# scd4x_rf-bm-2652p2.net
KiCad netlist of a schematic drawn in EAGLE
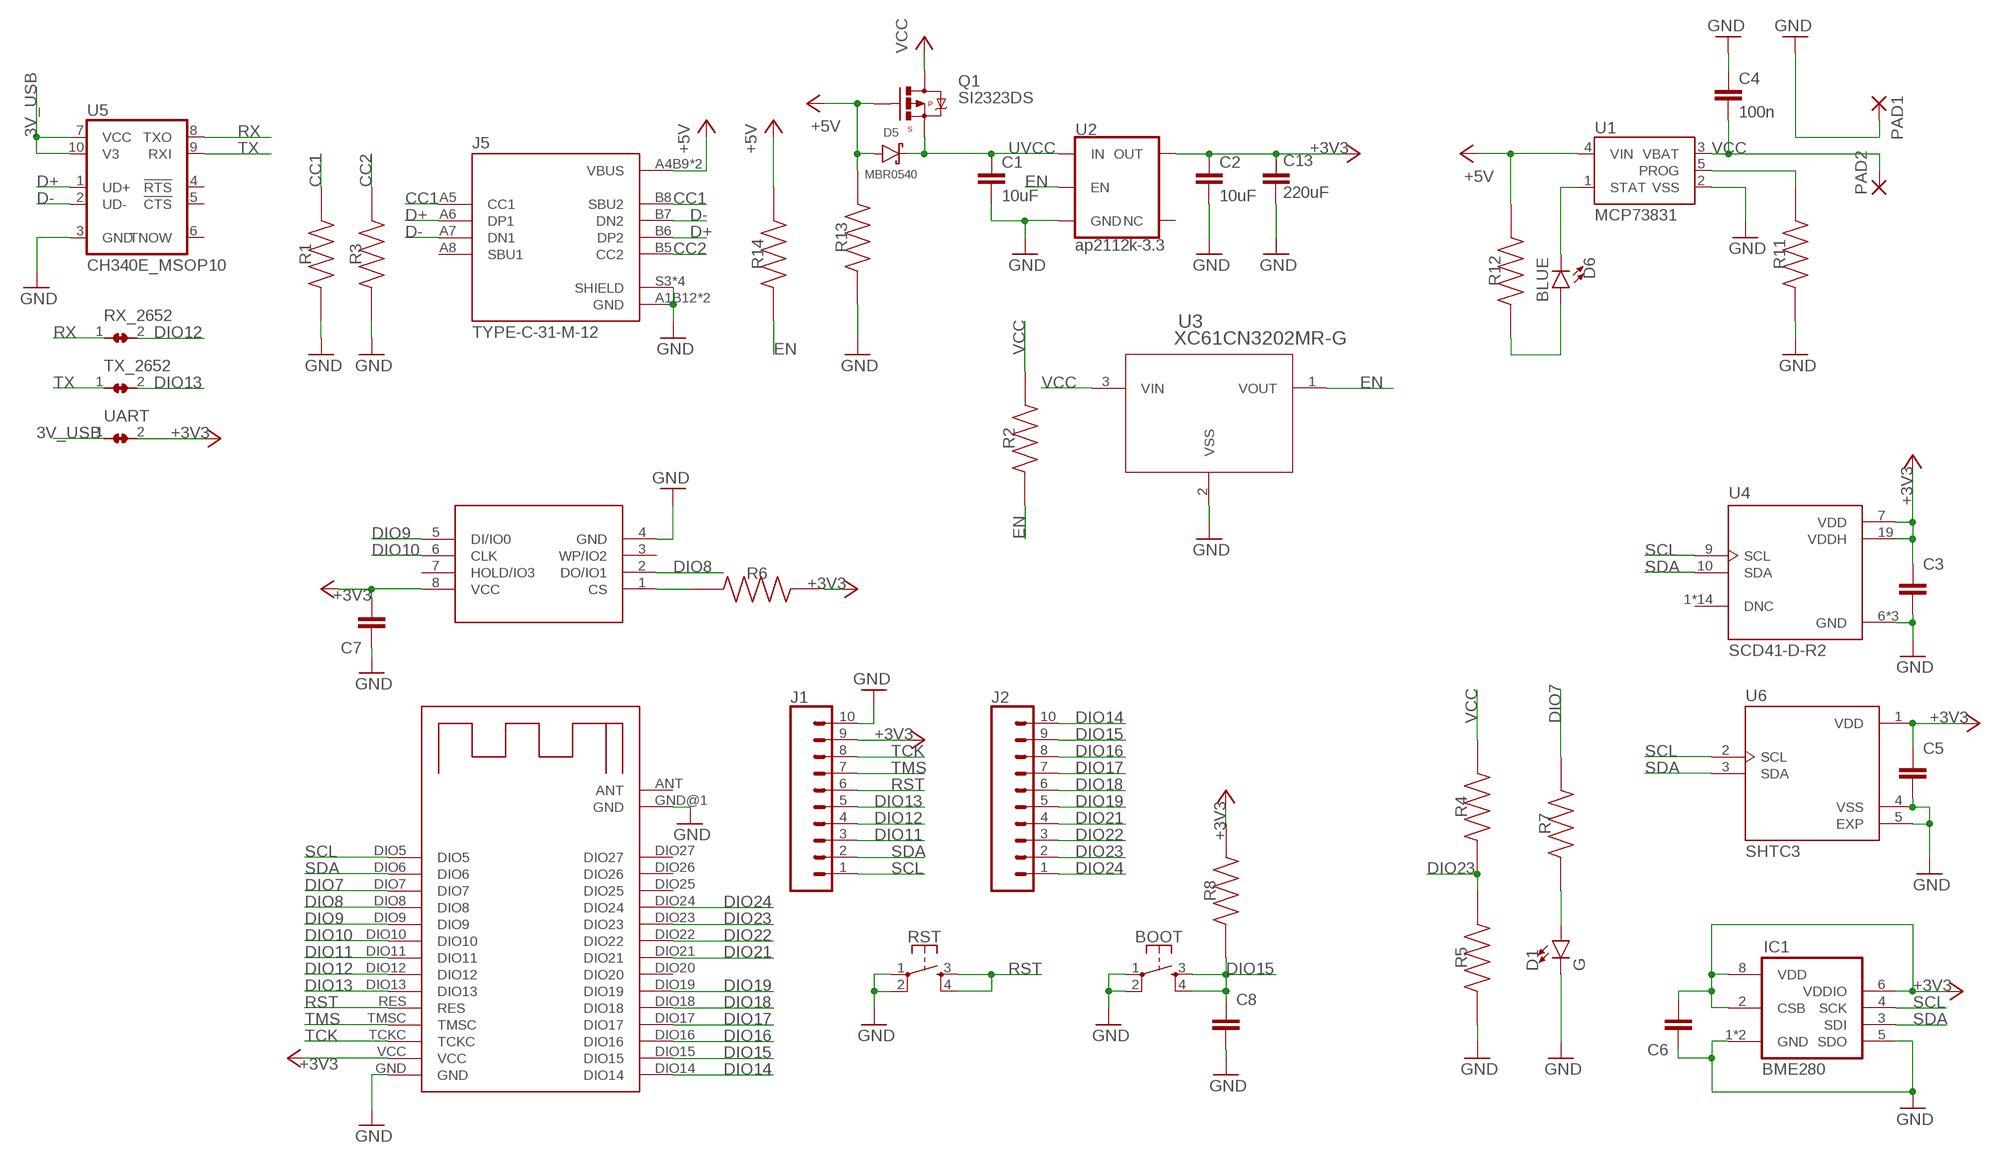
[diagram p0: schematic, sheet 1]

(export (version "E")
  (design (tool "Eeschema 10.0.6"))
  (components
    (comp (ref "BOOT")
      (value "MOMENTARY-SWITCH-SPST-2-SMD-4.6X2.8MM")
      (footprint "eagle-import:TACTILE_SWITCH_SMD_4.6X2.8MM")
      (libsource (lib "eagle-import") (part "MOMENTARY-SWITCH-SPST-2-SMD-4.6X2.8MM"))
    )
    (comp (ref "C1")
      (value "10uF")
      (footprint "eagle-import:0603")
      (libsource (lib "eagle-import") (part "10UF-0603-6.3V-20%"))
    )
    (comp (ref "C2")
      (value "10uF")
      (footprint "eagle-import:0603")
      (libsource (lib "eagle-import") (part "10UF-0603-6.3V-20%"))
    )
    (comp (ref "C3")
      (value "100nF")
      (footprint "eagle-import:CAPC1005X40N")
      (fields (field (name "MF") "Yageo") (field (name "MP") "RC0402FR-073M6L"))
      (libsource (lib "eagle-import") (part "CAP0402"))
    )
    (comp (ref "C4")
      (value "100n")
      (footprint "eagle-import:0603")
      (libsource (lib "eagle-import") (part "10UF-0603-6.3V-20%"))
    )
    (comp (ref "C5")
      (value "100nF")
      (footprint "eagle-import:CAPC1005X40N")
      (fields (field (name "MF") "Yageo") (field (name "MP") "RC0402FR-073M6L"))
      (libsource (lib "eagle-import") (part "CAP0402"))
    )
    (comp (ref "C6")
      (value "100nF")
      (footprint "eagle-import:CAPC1005X40N")
      (fields (field (name "MF") "Yageo") (field (name "MP") "RC0402FR-073M6L"))
      (libsource (lib "eagle-import") (part "CAP0402"))
    )
    (comp (ref "C7")
      (value "100n")
      (footprint "eagle-import:CAPC1005X40N")
      (fields (field (name "MF") "Yageo") (field (name "MP") "RC0402FR-073M6L"))
      (libsource (lib "eagle-import") (part "CAP0402"))
    )
    (comp (ref "C8")
      (value "100nF")
      (footprint "eagle-import:CAPC1005X40N")
      (fields (field (name "MF") "Yageo") (field (name "MP") "RC0402FR-073M6L"))
      (libsource (lib "eagle-import") (part "CAP0402"))
    )
    (comp (ref "C13")
      (value "220uF")
      (footprint "eagle-import:CAPM7343X310")
      (libsource (lib "eagle-import") (part "CTANTALUM-2917(7343-METRIC)_"))
    )
    (comp (ref "D1")
      (value "G")
      (footprint "eagle-import:LED-0603")
      (libsource (lib "eagle-import") (part "LED-BLUE0603"))
    )
    (comp (ref "D5")
      (value "MBR0540")
      (footprint "eagle-import:SOD-323")
      (libsource (lib "eagle-import") (part "DIODE-SCHOTTKY"))
    )
    (comp (ref "D6")
      (value "BLUE")
      (footprint "eagle-import:LED-0603")
      (libsource (lib "eagle-import") (part "LED-BLUE0603"))
    )
    (comp (ref "IC1")
      (value "BME280")
      (footprint "eagle-import:BME280")
      (libsource (lib "eagle-import") (part "BME280"))
    )
    (comp (ref "J1")
      (value "CONN_10NO_SILK_PTH_FEMALE")
      (footprint "eagle-import:1X10_NO_SILK")
      (libsource (lib "eagle-import") (part "CONN_10NO_SILK_PTH_FEMALE"))
    )
    (comp (ref "J2")
      (value "CONN_10NO_SILK_PTH_FEMALE")
      (footprint "eagle-import:1X10_NO_SILK")
      (libsource (lib "eagle-import") (part "CONN_10NO_SILK_PTH_FEMALE"))
    )
    (comp (ref "J5")
      (value "TYPE-C-31-M-12")
      (footprint "eagle-import:HRO_TYPE-C-31-M-12")
      (fields (field (name "MF") "HRO Electronics Co., Ltd."))
      (libsource (lib "eagle-import") (part "TYPE-C-31-M-12"))
    )
    (comp (ref "PAD1")
      (value "WIREPADSMD1,27-254")
      (footprint "eagle-import:SMD1,27-2,54")
      (libsource (lib "eagle-import") (part "WIREPADSMD1,27-254"))
    )
    (comp (ref "PAD2")
      (value "WIREPADSMD1,27-254")
      (footprint "eagle-import:SMD1,27-2,54")
      (libsource (lib "eagle-import") (part "WIREPADSMD1,27-254"))
    )
    (comp (ref "Q1")
      (value "SI2323DS")
      (footprint "eagle-import:SOT23")
      (libsource (lib "eagle-import") (part "MOSFET-PCHANNEL"))
    )
    (comp (ref "R1")
      (value "5.1k")
      (footprint "eagle-import:RESC1005X40N")
      (fields (field (name "MF") "Yageo") (field (name "MP") "RC0402FR-073M6L"))
      (libsource (lib "eagle-import") (part "RC0402FR-073M6L"))
    )
    (comp (ref "R2")
      (value "10k")
      (footprint "eagle-import:RESC1005X40N")
      (fields (field (name "MF") "Yageo") (field (name "MP") "RC0402FR-073M6L"))
      (libsource (lib "eagle-import") (part "RC0402FR-073M6L"))
    )
    (comp (ref "R3")
      (value "5.1k")
      (footprint "eagle-import:RESC1005X40N")
      (fields (field (name "MF") "Yageo") (field (name "MP") "RC0402FR-073M6L"))
      (libsource (lib "eagle-import") (part "RC0402FR-073M6L"))
    )
    (comp (ref "R4")
      (value "382k")
      (footprint "eagle-import:RESC1005X40N")
      (fields (field (name "MF") "Yageo") (field (name "MP") "RC0402FR-073M6L"))
      (libsource (lib "eagle-import") (part "RC0402FR-073M6L"))
    )
    (comp (ref "R5")
      (value "382k")
      (footprint "eagle-import:RESC1005X40N")
      (fields (field (name "MF") "Yageo") (field (name "MP") "RC0402FR-073M6L"))
      (libsource (lib "eagle-import") (part "RC0402FR-073M6L"))
    )
    (comp (ref "R6")
      (value "2.2k")
      (footprint "eagle-import:RESC1005X40N")
      (fields (field (name "MF") "Yageo") (field (name "MP") "RC0402FR-073M6L"))
      (libsource (lib "eagle-import") (part "RC0402FR-073M6L"))
    )
    (comp (ref "R7")
      (value "2.2k")
      (footprint "eagle-import:RESC1005X40N")
      (fields (field (name "MF") "Yageo") (field (name "MP") "RC0402FR-073M6L"))
      (libsource (lib "eagle-import") (part "RC0402FR-073M6L"))
    )
    (comp (ref "R8")
      (value "5.1M")
      (footprint "eagle-import:RESC1005X40N")
      (fields (field (name "MF") "Yageo") (field (name "MP") "RC0402FR-073M6L"))
      (libsource (lib "eagle-import") (part "RC0402FR-073M6L"))
    )
    (comp (ref "R11")
      (value "2k")
      (footprint "eagle-import:RESC1005X40N")
      (fields (field (name "MF") "Yageo") (field (name "MP") "RC0402FR-073M6L"))
      (libsource (lib "eagle-import") (part "RC0402FR-073M6L"))
    )
    (comp (ref "R12")
      (value "2.2k")
      (footprint "eagle-import:RESC1005X40N")
      (fields (field (name "MF") "Yageo") (field (name "MP") "RC0402FR-073M6L"))
      (libsource (lib "eagle-import") (part "RC0402FR-073M6L"))
    )
    (comp (ref "R13")
      (value "100k")
      (footprint "eagle-import:RESC1005X40N")
      (fields (field (name "MF") "Yageo") (field (name "MP") "RC0402FR-073M6L"))
      (libsource (lib "eagle-import") (part "RC0402FR-073M6L"))
    )
    (comp (ref "R14")
      (value "10k")
      (footprint "eagle-import:RESC1005X40N")
      (fields (field (name "MF") "Yageo") (field (name "MP") "RC0402FR-073M6L"))
      (libsource (lib "eagle-import") (part "RC0402FR-073M6L"))
    )
    (comp (ref "RST")
      (value "MOMENTARY-SWITCH-SPST-2-SMD-4.6X2.8MM")
      (footprint "eagle-import:TACTILE_SWITCH_SMD_4.6X2.8MM")
      (libsource (lib "eagle-import") (part "MOMENTARY-SWITCH-SPST-2-SMD-4.6X2.8MM"))
    )
    (comp (ref "RX_2652")
      (value "RX_2652")
      (footprint "eagle-import:SMALL_SOLDER_JUMPER_CLOSED")
      (libsource (lib "eagle-import") (part "SMALL_SOLDER_JUMPER_CLOSED"))
    )
    (comp (ref "TX_2652")
      (value "TX_2652")
      (footprint "eagle-import:SMALL_SOLDER_JUMPER_CLOSED")
      (libsource (lib "eagle-import") (part "SMALL_SOLDER_JUMPER_CLOSED"))
    )
    (comp (ref "U$1")
      (value "RF-BM-2652P2")
      (footprint "eagle-import:RF-BM-2652P2")
      (libsource (lib "eagle-import") (part "RF-BM-2652P2"))
    )
    (comp (ref "U$3")
      (value "MX25R8035FM1IL0")
      (footprint "eagle-import:SO-8")
      (fields (field (name "MF") "Winbond Electronics") (field (name "MP") "W25Q80BVSNIG"))
      (libsource (lib "eagle-import") (part "W25Q80BVSNIG"))
    )
    (comp (ref "U1")
      (value "MCP73831")
      (footprint "eagle-import:SOT23-5")
      (libsource (lib "eagle-import") (part "MCP73831"))
    )
    (comp (ref "U2")
      (value "ap2112k-3.3")
      (footprint "eagle-import:SOT23-5")
      (libsource (lib "eagle-import") (part "V_REG_AP2112K-3.3V"))
    )
    (comp (ref "U3")
      (value "XC61CN3202MR-G")
      (footprint "eagle-import:XC61C_SOT-23_TOR")
      (libsource (lib "eagle-import") (part "XC61CN3202MR-G"))
    )
    (comp (ref "U4")
      (value "SCD41-D-R2")
      (footprint "eagle-import:XDCR_SCD41-D-R2")
      (fields (field (name "MF") "Sensirion AG"))
      (libsource (lib "eagle-import") (part "SCD41-D-R2"))
    )
    (comp (ref "U5")
      (value "CH340E_MSOP10")
      (footprint "eagle-import:MSOP10")
      (fields (field (name "MF") "WCH") (field (name "MP") "CH340E"))
      (libsource (lib "eagle-import") (part "CH340E_MSOP10"))
    )
    (comp (ref "U6")
      (value "SHTC3")
      (footprint "eagle-import:SON100P200X200X80-5N")
      (fields (field (name "MF") "Sensirion AG"))
      (libsource (lib "eagle-import") (part "SHTC3"))
    )
    (comp (ref "UART")
      (value "UART")
      (footprint "eagle-import:SMALL_SOLDER_JUMPER_CLOSED")
      (libsource (lib "eagle-import") (part "SMALL_SOLDER_JUMPER_CLOSED"))
    )
  )
  (nets
    (net (code "1") (name "+3V3") (class "Default")
      (node (ref "C13") (pin "1") (pinfunction "1_1") (pintype "passive"))
      (node (ref "C2") (pin "1") (pinfunction "1_1") (pintype "passive"))
      (node (ref "C3") (pin "1") (pinfunction "1_1") (pintype "passive"))
      (node (ref "C5") (pin "1") (pinfunction "1_1") (pintype "passive"))
      (node (ref "C6") (pin "2") (pinfunction "2_2") (pintype "passive"))
      (node (ref "C7") (pin "2") (pinfunction "2_2") (pintype "passive"))
      (node (ref "IC1") (pin "2") (pinfunction "CSB_2") (pintype "input"))
      (node (ref "IC1") (pin "6") (pinfunction "VDDIO_6") (pintype "power_in"))
      (node (ref "IC1") (pin "8") (pinfunction "VDD_8") (pintype "power_in"))
      (node (ref "J1") (pin "9") (pinfunction "9_9") (pintype "passive"))
      (node (ref "R6") (pin "2") (pinfunction "2_2") (pintype "passive"))
      (node (ref "R8") (pin "2") (pinfunction "2_2") (pintype "passive"))
      (node (ref "U$1") (pin "VCC") (pinfunction "VCC_VCC") (pintype "bidirectional"))
      (node (ref "U$3") (pin "8") (pinfunction "VCC_8") (pintype "bidirectional"))
      (node (ref "U2") (pin "5") (pinfunction "OUT_5") (pintype "passive"))
      (node (ref "U4") (pin "19") (pinfunction "VDDH_19") (pintype "power_in"))
      (node (ref "U4") (pin "7") (pinfunction "VDD_7") (pintype "power_in"))
      (node (ref "U6") (pin "1") (pinfunction "VDD_1") (pintype "power_in"))
      (node (ref "UART") (pin "2") (pinfunction "2_2") (pintype "bidirectional"))
    )
    (net (code "2") (name "+5V") (class "Default")
      (node (ref "D5") (pin "A") (pinfunction "A_A") (pintype "passive"))
      (node (ref "J5") (pin "A4B9") (pinfunction "VBUS_A4B9") (pintype "power_in"))
      (node (ref "J5") (pin "B4A9") (pinfunction "VBUS_B4A9") (pintype "power_in"))
      (node (ref "Q1") (pin "1") (pinfunction "G_1") (pintype "passive"))
      (node (ref "R12") (pin "2") (pinfunction "2_2") (pintype "passive"))
      (node (ref "R13") (pin "2") (pinfunction "2_2") (pintype "passive"))
      (node (ref "R14") (pin "2") (pinfunction "2_2") (pintype "passive"))
      (node (ref "U1") (pin "4") (pinfunction "VIN_4") (pintype "power_in"))
    )
    (net (code "3") (name "/3V_USB") (class "Default")
      (node (ref "U5") (pin "10") (pinfunction "V3_10") (pintype "bidirectional"))
      (node (ref "U5") (pin "7") (pinfunction "VCC_7") (pintype "bidirectional"))
      (node (ref "UART") (pin "1") (pinfunction "1_1") (pintype "bidirectional"))
    )
    (net (code "4") (name "/CC1") (class "Default")
      (node (ref "J5") (pin "A5") (pinfunction "CC1_A5") (pintype "bidirectional"))
      (node (ref "J5") (pin "B8") (pinfunction "SBU2_B8") (pintype "bidirectional"))
      (node (ref "R1") (pin "2") (pinfunction "2_2") (pintype "passive"))
    )
    (net (code "5") (name "/CC2") (class "Default")
      (node (ref "J5") (pin "B5") (pinfunction "CC2_B5") (pintype "bidirectional"))
      (node (ref "R3") (pin "2") (pinfunction "2_2") (pintype "passive"))
    )
    (net (code "6") (name "/D+") (class "Default")
      (node (ref "J5") (pin "A6") (pinfunction "DP1_A6") (pintype "bidirectional"))
      (node (ref "J5") (pin "B6") (pinfunction "DP2_B6") (pintype "bidirectional"))
      (node (ref "U5") (pin "1") (pinfunction "UD+_1") (pintype "bidirectional"))
    )
    (net (code "7") (name "/D-") (class "Default")
      (node (ref "J5") (pin "A7") (pinfunction "DN1_A7") (pintype "bidirectional"))
      (node (ref "J5") (pin "B7") (pinfunction "DN2_B7") (pintype "bidirectional"))
      (node (ref "U5") (pin "2") (pinfunction "UD-_2") (pintype "bidirectional"))
    )
    (net (code "8") (name "/DIO7") (class "Default")
      (node (ref "R7") (pin "2") (pinfunction "2_2") (pintype "passive"))
      (node (ref "U$1") (pin "DIO7") (pinfunction "DIO7_DIO7") (pintype "bidirectional"))
    )
    (net (code "9") (name "/DIO8") (class "Default")
      (node (ref "U$1") (pin "DIO8") (pinfunction "DIO8_DIO8") (pintype "bidirectional"))
      (node (ref "U$3") (pin "2") (pinfunction "DO/IO1_2") (pintype "bidirectional"))
    )
    (net (code "10") (name "/DIO9") (class "Default")
      (node (ref "U$1") (pin "DIO9") (pinfunction "DIO9_DIO9") (pintype "bidirectional"))
      (node (ref "U$3") (pin "5") (pinfunction "DI/IO0_5") (pintype "bidirectional"))
    )
    (net (code "11") (name "/DIO10") (class "Default")
      (node (ref "U$1") (pin "DIO10") (pinfunction "DIO10_DIO10") (pintype "bidirectional"))
      (node (ref "U$3") (pin "6") (pinfunction "CLK_6") (pintype "bidirectional"))
    )
    (net (code "12") (name "/DIO11") (class "Default")
      (node (ref "J1") (pin "3") (pinfunction "3_3") (pintype "passive"))
      (node (ref "U$1") (pin "DIO11") (pinfunction "DIO11_DIO11") (pintype "bidirectional"))
    )
    (net (code "13") (name "/DIO12") (class "Default")
      (node (ref "J1") (pin "4") (pinfunction "4_4") (pintype "passive"))
      (node (ref "RX_2652") (pin "2") (pinfunction "2_2") (pintype "bidirectional"))
      (node (ref "U$1") (pin "DIO12") (pinfunction "DIO12_DIO12") (pintype "bidirectional"))
    )
    (net (code "14") (name "/DIO13") (class "Default")
      (node (ref "J1") (pin "5") (pinfunction "5_5") (pintype "passive"))
      (node (ref "TX_2652") (pin "2") (pinfunction "2_2") (pintype "bidirectional"))
      (node (ref "U$1") (pin "DIO13") (pinfunction "DIO13_DIO13") (pintype "bidirectional"))
    )
    (net (code "15") (name "/DIO14") (class "Default")
      (node (ref "J2") (pin "10") (pinfunction "10_10") (pintype "passive"))
      (node (ref "U$1") (pin "DIO14") (pinfunction "DIO14_DIO14") (pintype "bidirectional"))
    )
    (net (code "16") (name "/DIO15") (class "Default")
      (node (ref "BOOT") (pin "3") (pinfunction "3_3") (pintype "passive"))
      (node (ref "BOOT") (pin "4") (pinfunction "4_4") (pintype "passive"))
      (node (ref "C8") (pin "1") (pinfunction "1_1") (pintype "passive"))
      (node (ref "J2") (pin "9") (pinfunction "9_9") (pintype "passive"))
      (node (ref "R8") (pin "1") (pinfunction "1_1") (pintype "passive"))
      (node (ref "U$1") (pin "DIO15") (pinfunction "DIO15_DIO15") (pintype "bidirectional"))
    )
    (net (code "17") (name "/DIO16") (class "Default")
      (node (ref "J2") (pin "8") (pinfunction "8_8") (pintype "passive"))
      (node (ref "U$1") (pin "DIO16") (pinfunction "DIO16_DIO16") (pintype "bidirectional"))
    )
    (net (code "18") (name "/DIO17") (class "Default")
      (node (ref "J2") (pin "7") (pinfunction "7_7") (pintype "passive"))
      (node (ref "U$1") (pin "DIO17") (pinfunction "DIO17_DIO17") (pintype "bidirectional"))
    )
    (net (code "19") (name "/DIO18") (class "Default")
      (node (ref "J2") (pin "6") (pinfunction "6_6") (pintype "passive"))
      (node (ref "U$1") (pin "DIO18") (pinfunction "DIO18_DIO18") (pintype "bidirectional"))
    )
    (net (code "20") (name "/DIO19") (class "Default")
      (node (ref "J2") (pin "5") (pinfunction "5_5") (pintype "passive"))
      (node (ref "U$1") (pin "DIO19") (pinfunction "DIO19_DIO19") (pintype "bidirectional"))
    )
    (net (code "21") (name "/DIO21") (class "Default")
      (node (ref "J2") (pin "4") (pinfunction "4_4") (pintype "passive"))
      (node (ref "U$1") (pin "DIO21") (pinfunction "DIO21_DIO21") (pintype "bidirectional"))
    )
    (net (code "22") (name "/DIO22") (class "Default")
      (node (ref "J2") (pin "3") (pinfunction "3_3") (pintype "passive"))
      (node (ref "U$1") (pin "DIO22") (pinfunction "DIO22_DIO22") (pintype "bidirectional"))
    )
    (net (code "23") (name "/DIO23") (class "Default")
      (node (ref "J2") (pin "2") (pinfunction "2_2") (pintype "passive"))
      (node (ref "R4") (pin "1") (pinfunction "1_1") (pintype "passive"))
      (node (ref "R5") (pin "2") (pinfunction "2_2") (pintype "passive"))
      (node (ref "U$1") (pin "DIO23") (pinfunction "DIO23_DIO23") (pintype "bidirectional"))
    )
    (net (code "24") (name "/DIO24") (class "Default")
      (node (ref "J2") (pin "1") (pinfunction "1_1") (pintype "passive"))
      (node (ref "U$1") (pin "DIO24") (pinfunction "DIO24_DIO24") (pintype "bidirectional"))
    )
    (net (code "25") (name "/EN") (class "Default")
      (node (ref "R14") (pin "1") (pinfunction "1_1") (pintype "passive"))
      (node (ref "R2") (pin "1") (pinfunction "1_1") (pintype "passive"))
      (node (ref "U2") (pin "3") (pinfunction "EN_3") (pintype "input"))
      (node (ref "U3") (pin "1") (pinfunction "VOUT_1") (pintype "output"))
    )
    (net (code "26") (name "/RST") (class "Default")
      (node (ref "J1") (pin "6") (pinfunction "6_6") (pintype "passive"))
      (node (ref "RST") (pin "3") (pinfunction "3_3") (pintype "passive"))
      (node (ref "RST") (pin "4") (pinfunction "4_4") (pintype "passive"))
      (node (ref "U$1") (pin "RES") (pinfunction "RES_RES") (pintype "bidirectional"))
    )
    (net (code "27") (name "/RX") (class "Default")
      (node (ref "RX_2652") (pin "1") (pinfunction "1_1") (pintype "bidirectional"))
      (node (ref "U5") (pin "8") (pinfunction "TXO_8") (pintype "bidirectional"))
    )
    (net (code "28") (name "/SCL") (class "Default")
      (node (ref "IC1") (pin "4") (pinfunction "SCK_4") (pintype "bidirectional"))
      (node (ref "J1") (pin "1") (pinfunction "1_1") (pintype "passive"))
      (node (ref "U$1") (pin "DIO5") (pinfunction "DIO5_DIO5") (pintype "bidirectional"))
      (node (ref "U4") (pin "9") (pinfunction "SCL_9") (pintype "input"))
      (node (ref "U6") (pin "2") (pinfunction "SCL_2") (pintype "bidirectional"))
    )
    (net (code "29") (name "/SDA") (class "Default")
      (node (ref "IC1") (pin "3") (pinfunction "SDI_3") (pintype "bidirectional"))
      (node (ref "J1") (pin "2") (pinfunction "2_2") (pintype "passive"))
      (node (ref "U$1") (pin "DIO6") (pinfunction "DIO6_DIO6") (pintype "bidirectional"))
      (node (ref "U4") (pin "10") (pinfunction "SDA_10") (pintype "bidirectional"))
      (node (ref "U6") (pin "3") (pinfunction "SDA_3") (pintype "bidirectional"))
    )
    (net (code "30") (name "/TCK") (class "Default")
      (node (ref "J1") (pin "8") (pinfunction "8_8") (pintype "passive"))
      (node (ref "U$1") (pin "TCKC") (pinfunction "TCKC_TCKC") (pintype "bidirectional"))
    )
    (net (code "31") (name "/TMS") (class "Default")
      (node (ref "J1") (pin "7") (pinfunction "7_7") (pintype "passive"))
      (node (ref "U$1") (pin "TMSC") (pinfunction "TMSC_TMSC") (pintype "bidirectional"))
    )
    (net (code "32") (name "/TX") (class "Default")
      (node (ref "TX_2652") (pin "1") (pinfunction "1_1") (pintype "bidirectional"))
      (node (ref "U5") (pin "9") (pinfunction "RXI_9") (pintype "bidirectional"))
    )
    (net (code "33") (name "/UVCC") (class "Default")
      (node (ref "C1") (pin "1") (pinfunction "1_1") (pintype "passive"))
      (node (ref "D5") (pin "C") (pinfunction "C_C") (pintype "passive"))
      (node (ref "Q1") (pin "2") (pinfunction "S_2") (pintype "passive"))
      (node (ref "U2") (pin "1") (pinfunction "IN_1") (pintype "input"))
    )
    (net (code "34") (name "GND") (class "Default")
      (node (ref "BOOT") (pin "1") (pinfunction "1_1") (pintype "passive"))
      (node (ref "BOOT") (pin "2") (pinfunction "2_2") (pintype "passive"))
      (node (ref "C1") (pin "2") (pinfunction "2_2") (pintype "passive"))
      (node (ref "C13") (pin "2") (pinfunction "2_2") (pintype "passive"))
      (node (ref "C2") (pin "2") (pinfunction "2_2") (pintype "passive"))
      (node (ref "C3") (pin "2") (pinfunction "2_2") (pintype "passive"))
      (node (ref "C4") (pin "1") (pinfunction "1_1") (pintype "passive"))
      (node (ref "C5") (pin "2") (pinfunction "2_2") (pintype "passive"))
      (node (ref "C6") (pin "1") (pinfunction "1_1") (pintype "passive"))
      (node (ref "C7") (pin "1") (pinfunction "1_1") (pintype "passive"))
      (node (ref "C8") (pin "2") (pinfunction "2_2") (pintype "passive"))
      (node (ref "D1") (pin "C") (pinfunction "C_C") (pintype "passive"))
      (node (ref "IC1") (pin "1") (pinfunction "GND_1") (pintype "power_in"))
      (node (ref "IC1") (pin "5") (pinfunction "SDO_5") (pintype "input"))
      (node (ref "IC1") (pin "7") (pinfunction "GND_7") (pintype "power_in"))
      (node (ref "J1") (pin "10") (pinfunction "10_10") (pintype "passive"))
      (node (ref "J5") (pin "A1B12") (pinfunction "GND_A1B12") (pintype "power_in"))
      (node (ref "J5") (pin "B1A12") (pinfunction "GND_B1A12") (pintype "power_in"))
      (node (ref "J5") (pin "S3") (pinfunction "SHIELD_S3") (pintype "passive"))
      (node (ref "J5") (pin "S4") (pinfunction "SHIELD_S4") (pintype "passive"))
      (node (ref "J5") (pin "S5") (pinfunction "SHIELD_S5") (pintype "passive"))
      (node (ref "J5") (pin "S6") (pinfunction "SHIELD_S6") (pintype "passive"))
      (node (ref "PAD1") (pin "1") (pinfunction "P_1") (pintype "passive"))
      (node (ref "R1") (pin "1") (pinfunction "1_1") (pintype "passive"))
      (node (ref "R11") (pin "1") (pinfunction "1_1") (pintype "passive"))
      (node (ref "R13") (pin "1") (pinfunction "1_1") (pintype "passive"))
      (node (ref "R3") (pin "1") (pinfunction "1_1") (pintype "passive"))
      (node (ref "R5") (pin "1") (pinfunction "1_1") (pintype "passive"))
      (node (ref "RST") (pin "1") (pinfunction "1_1") (pintype "passive"))
      (node (ref "RST") (pin "2") (pinfunction "2_2") (pintype "passive"))
      (node (ref "U$1") (pin "GND") (pinfunction "GND_GND") (pintype "bidirectional"))
      (node (ref "U$1") (pin "GND@1") (pinfunction "GND_GND@1") (pintype "bidirectional"))
      (node (ref "U$3") (pin "4") (pinfunction "GND_4") (pintype "bidirectional"))
      (node (ref "U1") (pin "2") (pinfunction "VSS_2") (pintype "power_in"))
      (node (ref "U2") (pin "2") (pinfunction "GND_2") (pintype "input"))
      (node (ref "U3") (pin "2") (pinfunction "VSS_2") (pintype "passive"))
      (node (ref "U4") (pin "20") (pinfunction "GND_20") (pintype "power_in"))
      (node (ref "U4") (pin "21") (pinfunction "GND_21") (pintype "power_in"))
      (node (ref "U4") (pin "6") (pinfunction "GND_6") (pintype "power_in"))
      (node (ref "U5") (pin "3") (pinfunction "GND_3") (pintype "bidirectional"))
      (node (ref "U6") (pin "4") (pinfunction "VSS_4") (pintype "power_in"))
      (node (ref "U6") (pin "5") (pinfunction "EXP_5") (pintype "power_in"))
    )
    (net (code "35") (name "Net-(D1-PadA)") (class "Default")
      (node (ref "D1") (pin "A") (pinfunction "A_A") (pintype "passive"))
      (node (ref "R7") (pin "1") (pinfunction "1_1") (pintype "passive"))
    )
    (net (code "36") (name "Net-(D6-PadA)") (class "Default")
      (node (ref "D6") (pin "A") (pinfunction "A_A") (pintype "passive"))
      (node (ref "R12") (pin "1") (pinfunction "1_1") (pintype "passive"))
    )
    (net (code "37") (name "Net-(U$3-CS)") (class "Default")
      (node (ref "R6") (pin "1") (pinfunction "1_1") (pintype "passive"))
      (node (ref "U$3") (pin "1") (pinfunction "CS_1") (pintype "bidirectional"))
    )
    (net (code "38") (name "Net-(U1-PROG)") (class "Default")
      (node (ref "R11") (pin "2") (pinfunction "2_2") (pintype "passive"))
      (node (ref "U1") (pin "5") (pinfunction "PROG_5") (pintype "input"))
    )
    (net (code "39") (name "Net-(U1-STAT)") (class "Default")
      (node (ref "D6") (pin "C") (pinfunction "C_C") (pintype "passive"))
      (node (ref "U1") (pin "1") (pinfunction "STAT_1") (pintype "output"))
    )
    (net (code "40") (name "VCC") (class "Default")
      (node (ref "C4") (pin "2") (pinfunction "2_2") (pintype "passive"))
      (node (ref "PAD2") (pin "1") (pinfunction "P_1") (pintype "passive"))
      (node (ref "Q1") (pin "3") (pinfunction "D_3") (pintype "passive"))
      (node (ref "R2") (pin "2") (pinfunction "2_2") (pintype "passive"))
      (node (ref "R4") (pin "2") (pinfunction "2_2") (pintype "passive"))
      (node (ref "U1") (pin "3") (pinfunction "VBAT_3") (pintype "power_in"))
      (node (ref "U3") (pin "3") (pinfunction "VIN_3") (pintype "power_in"))
    )
    (net (code "41") (name "unconnected-(J5-SBU1-PadA8)") (class "Default")
      (node (ref "J5") (pin "A8") (pinfunction "SBU1_A8") (pintype "bidirectional"))
    )
    (net (code "42") (name "unconnected-(U$1-PadANT)") (class "Default")
      (node (ref "U$1") (pin "ANT") (pinfunction "ANT_ANT") (pintype "bidirectional"))
    )
    (net (code "43") (name "unconnected-(U$1-PadDIO20)") (class "Default")
      (node (ref "U$1") (pin "DIO20") (pinfunction "DIO20_DIO20") (pintype "bidirectional"))
    )
    (net (code "44") (name "unconnected-(U$1-PadDIO25)") (class "Default")
      (node (ref "U$1") (pin "DIO25") (pinfunction "DIO25_DIO25") (pintype "bidirectional"))
    )
    (net (code "45") (name "unconnected-(U$1-PadDIO26)") (class "Default")
      (node (ref "U$1") (pin "DIO26") (pinfunction "DIO26_DIO26") (pintype "bidirectional"))
    )
    (net (code "46") (name "unconnected-(U$1-PadDIO27)") (class "Default")
      (node (ref "U$1") (pin "DIO27") (pinfunction "DIO27_DIO27") (pintype "bidirectional"))
    )
    (net (code "47") (name "unconnected-(U$3-HOLD{slash}IO3-Pad7)") (class "Default")
      (node (ref "U$3") (pin "7") (pinfunction "HOLD/IO3_7") (pintype "bidirectional"))
    )
    (net (code "48") (name "unconnected-(U$3-WP{slash}IO2-Pad3)") (class "Default")
      (node (ref "U$3") (pin "3") (pinfunction "WP/IO2_3") (pintype "bidirectional"))
    )
    (net (code "49") (name "unconnected-(U2-NC-Pad4)") (class "Default")
      (node (ref "U2") (pin "4") (pinfunction "NC_4") (pintype "no_connect"))
    )
    (net (code "50") (name "unconnected-(U4-DNC-Pad1)") (class "Default")
      (node (ref "U4") (pin "1") (pinfunction "DNC_1") (pintype "no_connect"))
    )
    (net (code "51") (name "unconnected-(U4-DNC-Pad2)") (class "Default")
      (node (ref "U4") (pin "2") (pinfunction "DNC_2") (pintype "no_connect"))
    )
    (net (code "52") (name "unconnected-(U4-DNC-Pad3)") (class "Default")
      (node (ref "U4") (pin "3") (pinfunction "DNC_3") (pintype "no_connect"))
    )
    (net (code "53") (name "unconnected-(U4-DNC-Pad4)") (class "Default")
      (node (ref "U4") (pin "4") (pinfunction "DNC_4") (pintype "no_connect"))
    )
    (net (code "54") (name "unconnected-(U4-DNC-Pad5)") (class "Default")
      (node (ref "U4") (pin "5") (pinfunction "DNC_5") (pintype "no_connect"))
    )
    (net (code "55") (name "unconnected-(U4-DNC-Pad8)") (class "Default")
      (node (ref "U4") (pin "8") (pinfunction "DNC_8") (pintype "no_connect"))
    )
    (net (code "56") (name "unconnected-(U4-DNC-Pad11)") (class "Default")
      (node (ref "U4") (pin "11") (pinfunction "DNC_11") (pintype "no_connect"))
    )
    (net (code "57") (name "unconnected-(U4-DNC-Pad12)") (class "Default")
      (node (ref "U4") (pin "12") (pinfunction "DNC_12") (pintype "no_connect"))
    )
    (net (code "58") (name "unconnected-(U4-DNC-Pad13)") (class "Default")
      (node (ref "U4") (pin "13") (pinfunction "DNC_13") (pintype "no_connect"))
    )
    (net (code "59") (name "unconnected-(U4-DNC-Pad14)") (class "Default")
      (node (ref "U4") (pin "14") (pinfunction "DNC_14") (pintype "no_connect"))
    )
    (net (code "60") (name "unconnected-(U4-DNC-Pad15)") (class "Default")
      (node (ref "U4") (pin "15") (pinfunction "DNC_15") (pintype "no_connect"))
    )
    (net (code "61") (name "unconnected-(U4-DNC-Pad16)") (class "Default")
      (node (ref "U4") (pin "16") (pinfunction "DNC_16") (pintype "no_connect"))
    )
    (net (code "62") (name "unconnected-(U4-DNC-Pad17)") (class "Default")
      (node (ref "U4") (pin "17") (pinfunction "DNC_17") (pintype "no_connect"))
    )
    (net (code "63") (name "unconnected-(U4-DNC-Pad18)") (class "Default")
      (node (ref "U4") (pin "18") (pinfunction "DNC_18") (pintype "no_connect"))
    )
    (net (code "64") (name "unconnected-(U5-TNOW-Pad6)") (class "Default")
      (node (ref "U5") (pin "6") (pinfunction "TNOW_6") (pintype "bidirectional"))
    )
    (net (code "65") (name "unconnected-(U5-~{CTS}-Pad5)") (class "Default")
      (node (ref "U5") (pin "5") (pinfunction "~{CTS}_5") (pintype "bidirectional"))
    )
    (net (code "66") (name "unconnected-(U5-~{RTS}-Pad4)") (class "Default")
      (node (ref "U5") (pin "4") (pinfunction "~{RTS}_4") (pintype "bidirectional"))
    )
  )
)
